# obc-v2_EXP-CAN-RS422.net
KiCad netlist of a schematic drawn in Altium Designer
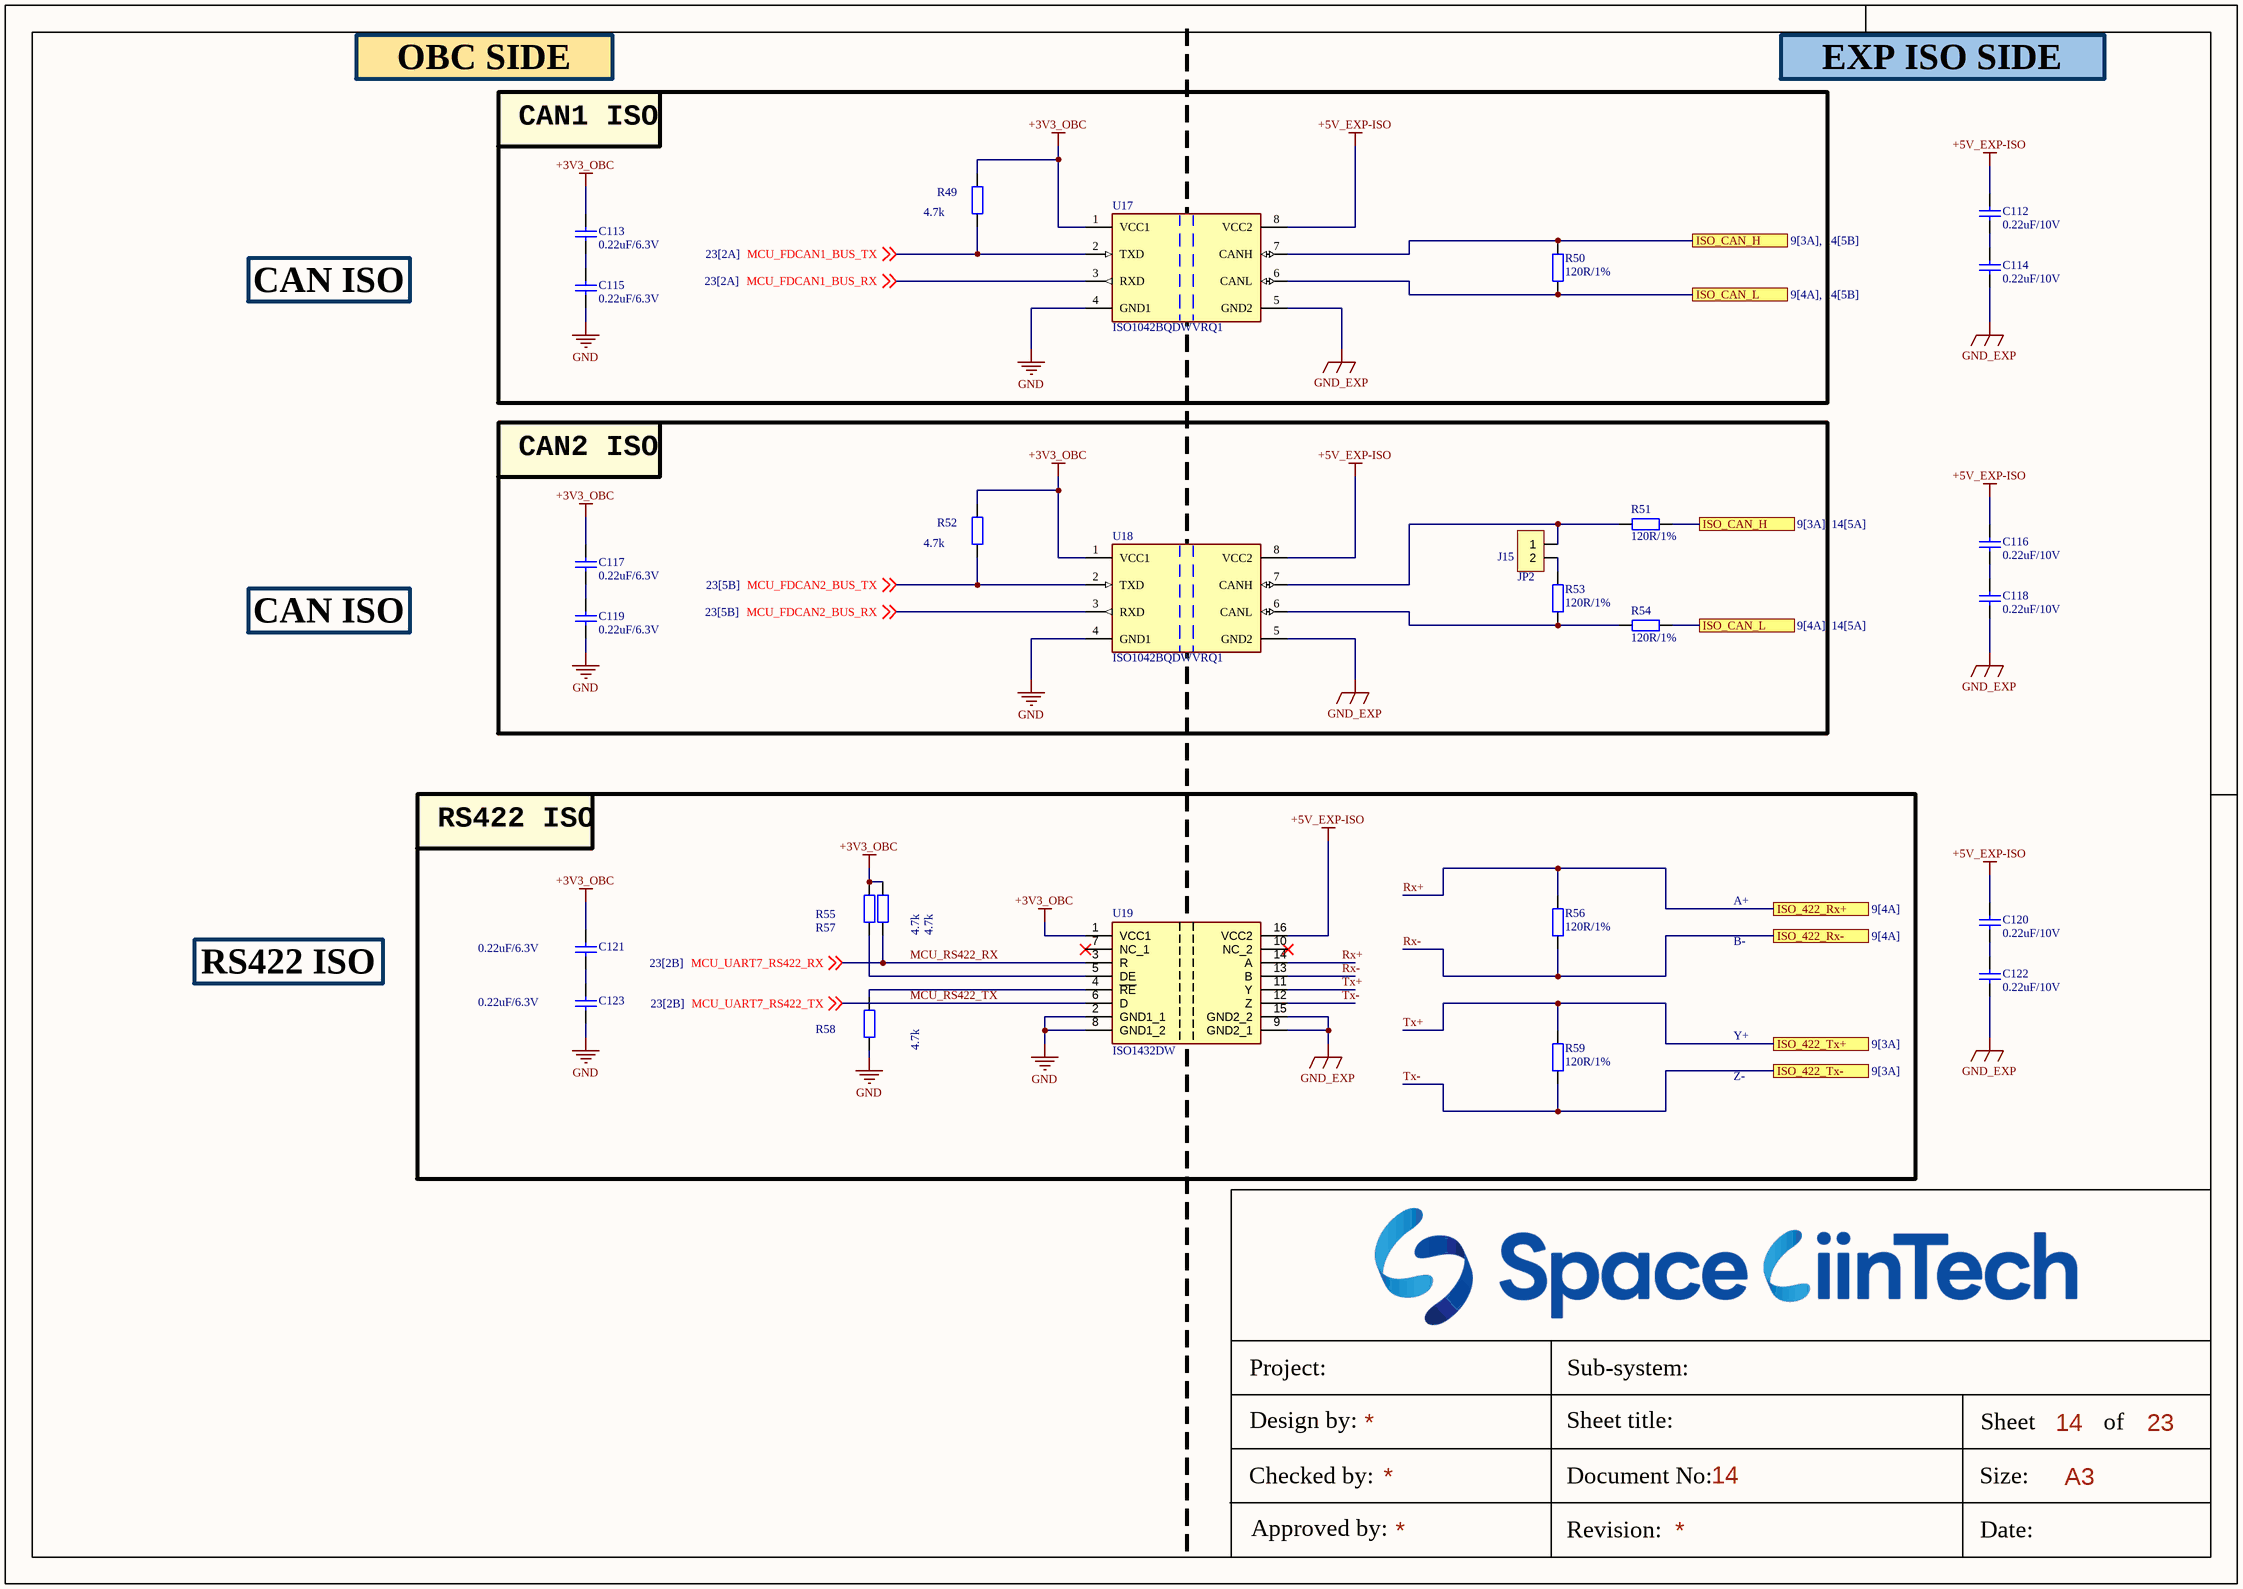
[diagram p0: obc-v2_EXP-CAN-RS422.SchDoc]

(export (version "E")
  (design (tool "Eeschema 10.0.6"))
  (components
    (comp (ref "C112")
      (value "0.22uF/10V")
      (footprint "CAP_C_1005X60")
      (description "CAPC")
      (libsource (lib "Altium_Lib_by_KhueNguyenCreator") (part "Tu 0402 33nF 10V"))
    )
    (comp (ref "C113")
      (value "0.22uF/6.3V")
      (footprint "CAP_C_1005X60")
      (description "CAPC")
      (libsource (lib "Altium_Lib_by_KhueNguyenCreator") (part "Tu 0402 33nF 10V"))
    )
    (comp (ref "C114")
      (value "0.22uF/10V")
      (footprint "CAP_C_1005X60")
      (description "CAPC")
      (libsource (lib "Altium_Lib_by_KhueNguyenCreator") (part "Tu 0402 33nF 10V"))
    )
    (comp (ref "C115")
      (value "0.22uF/6.3V")
      (footprint "CAP_C_1005X60")
      (description "CAPC")
      (libsource (lib "Altium_Lib_by_KhueNguyenCreator") (part "Tu 0402 33nF 10V"))
    )
    (comp (ref "C116")
      (value "0.22uF/10V")
      (footprint "CAP_C_1005X60")
      (description "CAPC")
      (libsource (lib "Altium_Lib_by_KhueNguyenCreator") (part "Tu 0402 33nF 10V"))
    )
    (comp (ref "C117")
      (value "0.22uF/6.3V")
      (footprint "CAP_C_1005X60")
      (description "CAPC")
      (libsource (lib "Altium_Lib_by_KhueNguyenCreator") (part "Tu 0402 33nF 10V"))
    )
    (comp (ref "C118")
      (value "0.22uF/10V")
      (footprint "CAP_C_1005X60")
      (description "CAPC")
      (libsource (lib "Altium_Lib_by_KhueNguyenCreator") (part "Tu 0402 33nF 10V"))
    )
    (comp (ref "C119")
      (value "0.22uF/6.3V")
      (footprint "CAP_C_1005X60")
      (description "CAPC")
      (libsource (lib "Altium_Lib_by_KhueNguyenCreator") (part "Tu 0402 33nF 10V"))
    )
    (comp (ref "C120")
      (value "0.22uF/10V")
      (footprint "CAP_C_1005X60")
      (description "CAPC")
      (libsource (lib "Altium_Lib_by_KhueNguyenCreator") (part "Tu 0402 33nF 10V"))
    )
    (comp (ref "C121")
      (value "0.22uF/6.3V")
      (footprint "CAP_C_1005X60")
      (description "CAPC")
      (libsource (lib "Altium_Lib_by_KhueNguyenCreator") (part "Tu 0402 33nF 10V"))
    )
    (comp (ref "C122")
      (value "0.22uF/10V")
      (footprint "CAP_C_1005X60")
      (description "CAPC")
      (libsource (lib "Altium_Lib_by_KhueNguyenCreator") (part "Tu 0402 33nF 10V"))
    )
    (comp (ref "C123")
      (value "0.22uF/6.3V")
      (footprint "CAP_C_1005X60")
      (description "CAPC")
      (libsource (lib "Altium_Lib_by_KhueNguyenCreator") (part "Tu 0402 33nF 10V"))
    )
    (comp (ref "J15")
      (value "JP2")
      (footprint "JP2-D1T")
      (description "WR-PHD 2.54 mm Angled Socket Header")
      (fields
        (field (name "MANUFACTURER") "Würth Elektronik eiSos GmbH")
        (field (name "PARTNO") "613002143121")
        (field (name "CREATED BY") "Karrer Zheng")
      )
      (libsource (lib "TechMT.VN_Lib") (part "JP2"))
    )
    (comp (ref "R49")
      (value "4.7k")
      (footprint "RES_C_1608X60")
      (description "RES")
      (libsource (lib "Altium_Lib_by_KhueNguyenCreator") (part "Tro 0603 1% 10k"))
    )
    (comp (ref "R50")
      (value "120R/1%")
      (footprint "RES_C_1608X60")
      (description "RES")
      (libsource (lib "Altium_Lib_by_KhueNguyenCreator") (part "Tro 0603 1% 10k"))
    )
    (comp (ref "R51")
      (value "120R/1%")
      (footprint "RES_C_1608X60")
      (description "RES")
      (libsource (lib "Altium_Lib_by_KhueNguyenCreator") (part "Tro 0603 1% 10k"))
    )
    (comp (ref "R52")
      (value "4.7k")
      (footprint "RES_C_1608X60")
      (description "RES")
      (libsource (lib "Altium_Lib_by_KhueNguyenCreator") (part "Tro 0603 1% 10k"))
    )
    (comp (ref "R53")
      (value "120R/1%")
      (footprint "RES_C_1608X60")
      (description "RES")
      (libsource (lib "Altium_Lib_by_KhueNguyenCreator") (part "Tro 0603 1% 10k"))
    )
    (comp (ref "R54")
      (value "120R/1%")
      (footprint "RES_C_1608X60")
      (description "RES")
      (libsource (lib "Altium_Lib_by_KhueNguyenCreator") (part "Tro 0603 1% 10k"))
    )
    (comp (ref "R55")
      (value "4.7k")
      (footprint "RES_C_1608X60")
      (description "RES")
      (libsource (lib "Altium_Lib_by_KhueNguyenCreator") (part "Tro 0603 1% 10k"))
    )
    (comp (ref "R56")
      (value "120R/1%")
      (footprint "RES_C_1608X60")
      (description "RES")
      (libsource (lib "Altium_Lib_by_KhueNguyenCreator") (part "Tro 0603 1% 10k"))
    )
    (comp (ref "R57")
      (value "4.7k")
      (footprint "RES_C_1608X60")
      (description "RES")
      (libsource (lib "Altium_Lib_by_KhueNguyenCreator") (part "Tro 0603 1% 10k"))
    )
    (comp (ref "R58")
      (value "4.7k")
      (footprint "RES_C_1608X60")
      (description "RES")
      (libsource (lib "Altium_Lib_by_KhueNguyenCreator") (part "Tro 0603 1% 10k"))
    )
    (comp (ref "R59")
      (value "120R/1%")
      (footprint "RES_C_1608X60")
      (description "RES")
      (libsource (lib "Altium_Lib_by_KhueNguyenCreator") (part "Tro 0603 1% 10k"))
    )
    (comp (ref "U17")
      (value "ISO1042BQDWVRQ1")
      (footprint "FP-DWV0008A-IPC_B")
      (description "TRANSCEIVER")
      (libsource (lib "Altium Content Vault") (part "fe23ea8f5f5d7467cd303882fedab7a"))
    )
    (comp (ref "U18")
      (value "ISO1042BQDWVRQ1")
      (footprint "FP-DWV0008A-IPC_B")
      (description "TRANSCEIVER")
      (libsource (lib "Altium Content Vault") (part "fe23ea8f5f5d7467cd303882fedab7a"))
    )
    (comp (ref "U19")
      (value "ISO1432DW")
      (footprint "SOIC127P1030X265-16N")
      (fields
        (field (name "MANUFACTURER_PART_NUMBER") "ISO1430DW")
        (field (name "MOUSER PART NUMBER") "595-ISO1430DW")
      )
      (libsource (lib "ISO1432DWRiso") (part "ISO1432DWR"))
    )
  )
  (nets
    (net (code "1") (name "+3V3_OBC") (class "Default")
      (node (ref "C113") (pin "1") (pinfunction "1_1") (pintype "passive"))
      (node (ref "C117") (pin "1") (pinfunction "1_1") (pintype "passive"))
      (node (ref "C121") (pin "1") (pinfunction "1_1") (pintype "passive"))
      (node (ref "R49") (pin "2") (pinfunction "2_2") (pintype "passive"))
      (node (ref "R52") (pin "2") (pinfunction "2_2") (pintype "passive"))
      (node (ref "R55") (pin "2") (pinfunction "2_2") (pintype "passive"))
      (node (ref "R57") (pin "2") (pinfunction "2_2") (pintype "passive"))
      (node (ref "U17") (pin "1") (pinfunction "VCC1_1") (pintype "power_in"))
      (node (ref "U18") (pin "1") (pinfunction "VCC1_1") (pintype "power_in"))
      (node (ref "U19") (pin "1") (pinfunction "VCC1_1") (pintype "power_in"))
    )
    (net (code "2") (name "+5V_EXP-ISO") (class "Default")
      (node (ref "C112") (pin "1") (pinfunction "1_1") (pintype "passive"))
      (node (ref "C116") (pin "1") (pinfunction "1_1") (pintype "passive"))
      (node (ref "C120") (pin "2") (pinfunction "2_2") (pintype "passive"))
      (node (ref "U17") (pin "8") (pinfunction "VCC2_8") (pintype "power_in"))
      (node (ref "U18") (pin "8") (pinfunction "VCC2_8") (pintype "power_in"))
      (node (ref "U19") (pin "16") (pinfunction "VCC2_16") (pintype "power_in"))
    )
    (net (code "3") (name "/ISO_CAN_H") (class "Default")
      (node (ref "R50") (pin "2") (pinfunction "2_2") (pintype "passive"))
      (node (ref "R51") (pin "1") (pinfunction "1_1") (pintype "passive"))
      (node (ref "U17") (pin "7") (pinfunction "CANH_7") (pintype "bidirectional"))
    )
    (net (code "4") (name "/ISO_CAN_L") (class "Default")
      (node (ref "R50") (pin "1") (pinfunction "1_1") (pintype "passive"))
      (node (ref "R54") (pin "1") (pinfunction "1_1") (pintype "passive"))
      (node (ref "U17") (pin "6") (pinfunction "CANL_6") (pintype "bidirectional"))
    )
    (net (code "5") (name "/Rx+") (class "Default")
      (node (ref "R56") (pin "2") (pinfunction "2_2") (pintype "passive"))
      (node (ref "U19") (pin "14") (pinfunction "A_14") (pintype "passive"))
    )
    (net (code "6") (name "/Rx-") (class "Default")
      (node (ref "R56") (pin "1") (pinfunction "1_1") (pintype "passive"))
      (node (ref "U19") (pin "13") (pinfunction "B_13") (pintype "passive"))
    )
    (net (code "7") (name "/Tx+") (class "Default")
      (node (ref "R59") (pin "2") (pinfunction "2_2") (pintype "passive"))
      (node (ref "U19") (pin "11") (pinfunction "Y_11") (pintype "passive"))
    )
    (net (code "8") (name "/Tx-") (class "Default")
      (node (ref "R59") (pin "1") (pinfunction "1_1") (pintype "passive"))
      (node (ref "U19") (pin "12") (pinfunction "Z_12") (pintype "passive"))
    )
    (net (code "9") (name "GND") (class "Default")
      (node (ref "C115") (pin "2") (pinfunction "2_2") (pintype "passive"))
      (node (ref "C119") (pin "2") (pinfunction "2_2") (pintype "passive"))
      (node (ref "C123") (pin "2") (pinfunction "2_2") (pintype "passive"))
      (node (ref "R58") (pin "1") (pinfunction "1_1") (pintype "passive"))
      (node (ref "U17") (pin "4") (pinfunction "GND1_4") (pintype "power_in"))
      (node (ref "U18") (pin "4") (pinfunction "GND1_4") (pintype "power_in"))
      (node (ref "U19") (pin "2") (pinfunction "GND1_1_2") (pintype "passive"))
      (node (ref "U19") (pin "8") (pinfunction "GND1_2_8") (pintype "passive"))
    )
    (net (code "10") (name "GND_EXP") (class "Default")
      (node (ref "C114") (pin "2") (pinfunction "2_2") (pintype "passive"))
      (node (ref "C118") (pin "2") (pinfunction "2_2") (pintype "passive"))
      (node (ref "C122") (pin "1") (pinfunction "1_1") (pintype "passive"))
      (node (ref "U17") (pin "5") (pinfunction "GND2_5") (pintype "power_in"))
      (node (ref "U18") (pin "5") (pinfunction "GND2_5") (pintype "power_in"))
      (node (ref "U19") (pin "15") (pinfunction "GND2_2_15") (pintype "passive"))
      (node (ref "U19") (pin "9") (pinfunction "GND2_1_9") (pintype "passive"))
    )
    (net (code "11") (name "MCU_FDCAN1_BUS_RX") (class "Default")
      (node (ref "U17") (pin "3") (pinfunction "RXD_3") (pintype "output"))
    )
    (net (code "12") (name "MCU_FDCAN1_BUS_TX") (class "Default")
      (node (ref "R49") (pin "1") (pinfunction "1_1") (pintype "passive"))
      (node (ref "U17") (pin "2") (pinfunction "TXD_2") (pintype "input"))
    )
    (net (code "13") (name "MCU_FDCAN2_BUS_RX") (class "Default")
      (node (ref "U18") (pin "3") (pinfunction "RXD_3") (pintype "output"))
    )
    (net (code "14") (name "MCU_FDCAN2_BUS_TX") (class "Default")
      (node (ref "R52") (pin "1") (pinfunction "1_1") (pintype "passive"))
      (node (ref "U18") (pin "2") (pinfunction "TXD_2") (pintype "input"))
    )
    (net (code "15") (name "MCU_UART7_RS422_RX") (class "Default")
      (node (ref "R57") (pin "1") (pinfunction "1_1") (pintype "passive"))
      (node (ref "U19") (pin "3") (pinfunction "R_3") (pintype "passive"))
    )
    (net (code "16") (name "MCU_UART7_RS422_TX") (class "Default")
      (node (ref "U19") (pin "6") (pinfunction "D_6") (pintype "passive"))
    )
    (net (code "17") (name "Net-(C112-Pad2)") (class "Default")
      (node (ref "C112") (pin "2") (pinfunction "2_2") (pintype "passive"))
      (node (ref "C114") (pin "1") (pinfunction "1_1") (pintype "passive"))
    )
    (net (code "18") (name "Net-(C113-Pad2)") (class "Default")
      (node (ref "C113") (pin "2") (pinfunction "2_2") (pintype "passive"))
      (node (ref "C115") (pin "1") (pinfunction "1_1") (pintype "passive"))
    )
    (net (code "19") (name "Net-(C116-Pad2)") (class "Default")
      (node (ref "C116") (pin "2") (pinfunction "2_2") (pintype "passive"))
      (node (ref "C118") (pin "1") (pinfunction "1_1") (pintype "passive"))
    )
    (net (code "20") (name "Net-(C117-Pad2)") (class "Default")
      (node (ref "C117") (pin "2") (pinfunction "2_2") (pintype "passive"))
      (node (ref "C119") (pin "1") (pinfunction "1_1") (pintype "passive"))
    )
    (net (code "21") (name "Net-(C120-Pad1)") (class "Default")
      (node (ref "C120") (pin "1") (pinfunction "1_1") (pintype "passive"))
      (node (ref "C122") (pin "2") (pinfunction "2_2") (pintype "passive"))
    )
    (net (code "22") (name "Net-(C121-Pad2)") (class "Default")
      (node (ref "C121") (pin "2") (pinfunction "2_2") (pintype "passive"))
      (node (ref "C123") (pin "1") (pinfunction "1_1") (pintype "passive"))
    )
    (net (code "23") (name "Net-(J15-Pad2)") (class "Default")
      (node (ref "J15") (pin "2") (pinfunction "2_2") (pintype "passive"))
      (node (ref "R53") (pin "2") (pinfunction "2_2") (pintype "passive"))
    )
    (net (code "24") (name "Net-(U18-CANH)") (class "Default")
      (node (ref "J15") (pin "1") (pinfunction "1_1") (pintype "passive"))
      (node (ref "R51") (pin "2") (pinfunction "2_2") (pintype "passive"))
      (node (ref "U18") (pin "7") (pinfunction "CANH_7") (pintype "bidirectional"))
    )
    (net (code "25") (name "Net-(U18-CANL)") (class "Default")
      (node (ref "R53") (pin "1") (pinfunction "1_1") (pintype "passive"))
      (node (ref "R54") (pin "2") (pinfunction "2_2") (pintype "passive"))
      (node (ref "U18") (pin "6") (pinfunction "CANL_6") (pintype "bidirectional"))
    )
    (net (code "26") (name "Net-(U19-DE)") (class "Default")
      (node (ref "R55") (pin "1") (pinfunction "1_1") (pintype "passive"))
      (node (ref "U19") (pin "5") (pinfunction "DE_5") (pintype "passive"))
    )
    (net (code "27") (name "Net-(U19-~{RE})") (class "Default")
      (node (ref "R58") (pin "2") (pinfunction "2_2") (pintype "passive"))
      (node (ref "U19") (pin "4") (pinfunction "~{RE}_4") (pintype "passive"))
    )
    (net (code "28") (name "unconnected-(U19-NC_1-Pad7)") (class "Default")
      (node (ref "U19") (pin "7") (pinfunction "NC_1_7") (pintype "passive+no_connect"))
    )
    (net (code "29") (name "unconnected-(U19-NC_2-Pad10)") (class "Default")
      (node (ref "U19") (pin "10") (pinfunction "NC_2_10") (pintype "passive+no_connect"))
    )
  )
)
